# DrivewayLights.net
KiCad netlist of a schematic drawn in EAGLE
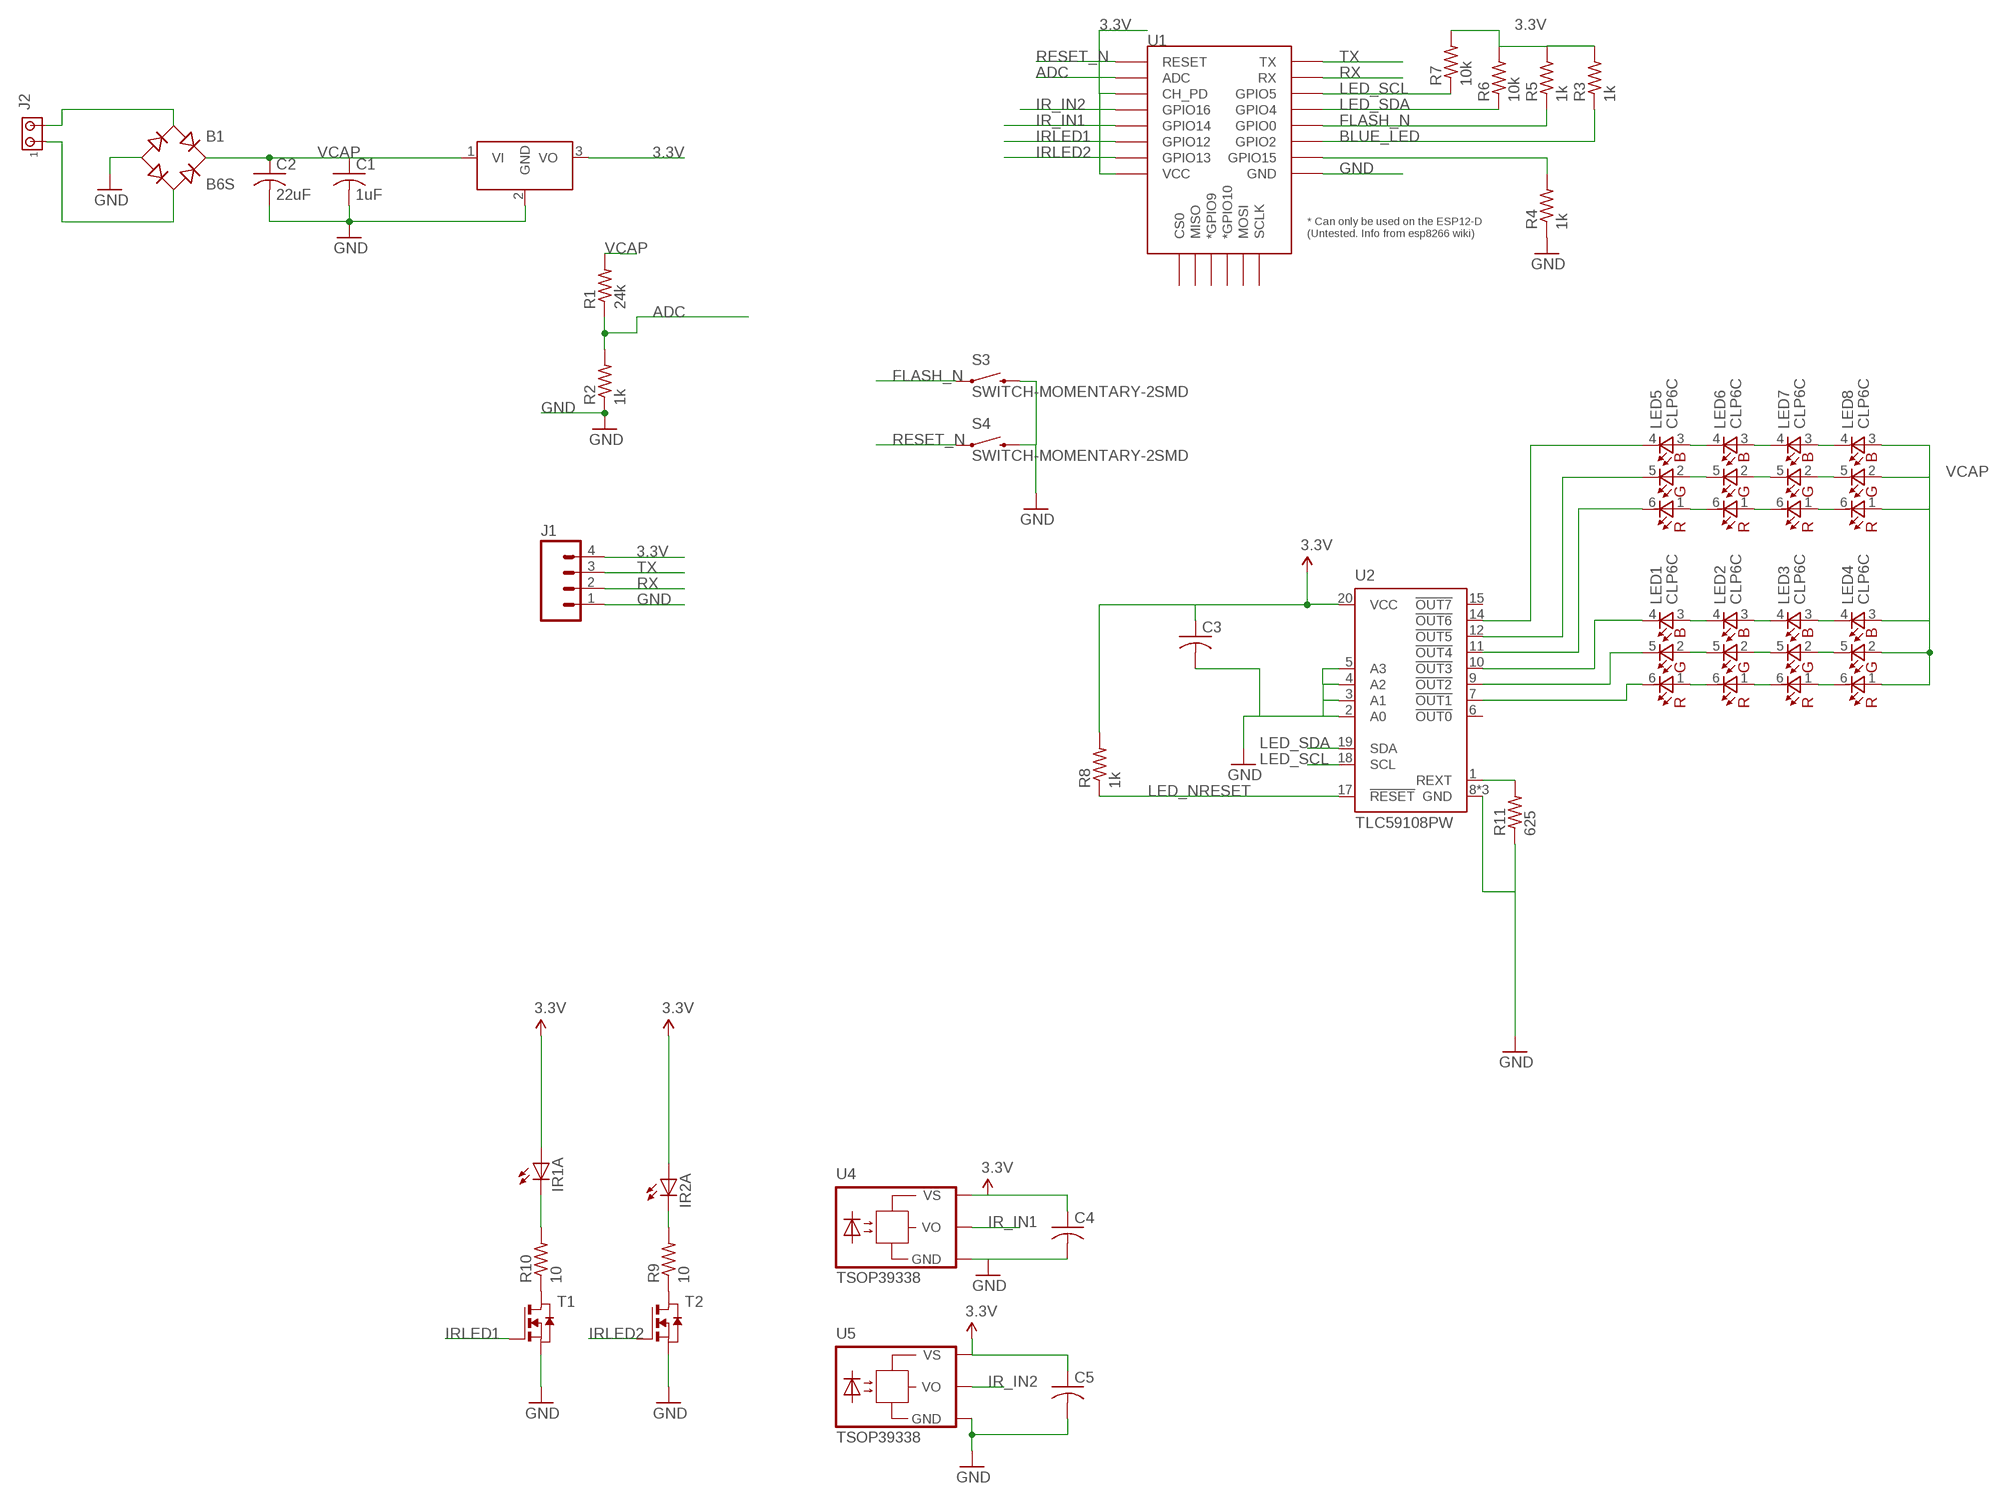
[diagram p0: schematic, sheet 1]

(export (version "E")
  (design (tool "Eeschema 10.0.6"))
  (components
    (comp (ref "B1")
      (value "B6S")
      (footprint "eagle-import:MBS")
      (libsource (lib "eagle-import") (part "BS6"))
    )
    (comp (ref "C1")
      (value "1uF")
      (footprint "eagle-import:C0805")
      (libsource (lib "eagle-import") (part "C-USC0805"))
    )
    (comp (ref "C2")
      (value "22uF")
      (footprint "eagle-import:C1210")
      (libsource (lib "eagle-import") (part "C-USC1210"))
    )
    (comp (ref "C3")
      (value "C-USC0603")
      (footprint "eagle-import:C0603")
      (libsource (lib "eagle-import") (part "C-USC0603"))
    )
    (comp (ref "C4")
      (value "C-USC0603")
      (footprint "eagle-import:C0603")
      (libsource (lib "eagle-import") (part "C-USC0603"))
    )
    (comp (ref "C5")
      (value "C-USC0603")
      (footprint "eagle-import:C0603")
      (libsource (lib "eagle-import") (part "C-USC0603"))
    )
    (comp (ref "IR1A")
      (value "LED5MM")
      (footprint "eagle-import:LED5MM")
      (libsource (lib "eagle-import") (part "LED5MM"))
    )
    (comp (ref "IR2A")
      (value "LED5MM")
      (footprint "eagle-import:LED5MM")
      (libsource (lib "eagle-import") (part "LED5MM"))
    )
    (comp (ref "J1")
      (value "M04JST-PTH-VERT")
      (footprint "eagle-import:JST-4-PTH-VERT")
      (libsource (lib "eagle-import") (part "M04JST-PTH-VERT"))
    )
    (comp (ref "J2")
      (value "MTA02-100")
      (footprint "eagle-import:10X02MTA")
      (libsource (lib "eagle-import") (part "MTA02-100"))
    )
    (comp (ref "LED1")
      (value "CLP6C")
      (footprint "eagle-import:CLP6C")
      (libsource (lib "eagle-import") (part "CLP6C"))
    )
    (comp (ref "LED2")
      (value "CLP6C")
      (footprint "eagle-import:CLP6C")
      (libsource (lib "eagle-import") (part "CLP6C"))
    )
    (comp (ref "LED3")
      (value "CLP6C")
      (footprint "eagle-import:CLP6C")
      (libsource (lib "eagle-import") (part "CLP6C"))
    )
    (comp (ref "LED4")
      (value "CLP6C")
      (footprint "eagle-import:CLP6C")
      (libsource (lib "eagle-import") (part "CLP6C"))
    )
    (comp (ref "LED5")
      (value "CLP6C")
      (footprint "eagle-import:CLP6C")
      (libsource (lib "eagle-import") (part "CLP6C"))
    )
    (comp (ref "LED6")
      (value "CLP6C")
      (footprint "eagle-import:CLP6C")
      (libsource (lib "eagle-import") (part "CLP6C"))
    )
    (comp (ref "LED7")
      (value "CLP6C")
      (footprint "eagle-import:CLP6C")
      (libsource (lib "eagle-import") (part "CLP6C"))
    )
    (comp (ref "LED8")
      (value "CLP6C")
      (footprint "eagle-import:CLP6C")
      (libsource (lib "eagle-import") (part "CLP6C"))
    )
    (comp (ref "R1")
      (value "24k")
      (footprint "eagle-import:R0603")
      (libsource (lib "eagle-import") (part "resistor_R-US_R0603"))
    )
    (comp (ref "R2")
      (value "1k")
      (footprint "eagle-import:R0603")
      (libsource (lib "eagle-import") (part "resistor_R-US_R0603"))
    )
    (comp (ref "R3")
      (value "1k")
      (footprint "eagle-import:R0603")
      (libsource (lib "eagle-import") (part "resistor_R-US_R0603"))
    )
    (comp (ref "R4")
      (value "1k")
      (footprint "eagle-import:R0603")
      (libsource (lib "eagle-import") (part "resistor_R-US_R0603"))
    )
    (comp (ref "R5")
      (value "1k")
      (footprint "eagle-import:R0603")
      (libsource (lib "eagle-import") (part "resistor_R-US_R0603"))
    )
    (comp (ref "R6")
      (value "10k")
      (footprint "eagle-import:R0603")
      (libsource (lib "eagle-import") (part "resistor_R-US_R0603"))
    )
    (comp (ref "R7")
      (value "10k")
      (footprint "eagle-import:R0603")
      (libsource (lib "eagle-import") (part "resistor_R-US_R0603"))
    )
    (comp (ref "R8")
      (value "1k")
      (footprint "eagle-import:R0603")
      (libsource (lib "eagle-import") (part "resistor_R-US_R0603"))
    )
    (comp (ref "R9")
      (value "10")
      (footprint "eagle-import:R0603")
      (libsource (lib "eagle-import") (part "R-US_R0603"))
    )
    (comp (ref "R10")
      (value "10")
      (footprint "eagle-import:R0603")
      (libsource (lib "eagle-import") (part "R-US_R0603"))
    )
    (comp (ref "R11")
      (value "625")
      (footprint "eagle-import:R0603")
      (libsource (lib "eagle-import") (part "R-US_R0603"))
    )
    (comp (ref "S3")
      (value "SWITCH-MOMENTARY-2SMD")
      (footprint "eagle-import:TACTILE-SWITCH-SMD")
      (libsource (lib "eagle-import") (part "SWITCH-MOMENTARY-2SMD"))
    )
    (comp (ref "S4")
      (value "SWITCH-MOMENTARY-2SMD")
      (footprint "eagle-import:TACTILE-SWITCH-SMD")
      (libsource (lib "eagle-import") (part "SWITCH-MOMENTARY-2SMD"))
    )
    (comp (ref "T1")
      (value "NMOSSOT23")
      (footprint "eagle-import:SOT-23")
      (libsource (lib "eagle-import") (part "NMOSSOT23"))
    )
    (comp (ref "T2")
      (value "NMOSSOT23")
      (footprint "eagle-import:SOT-23")
      (libsource (lib "eagle-import") (part "NMOSSOT23"))
    )
    (comp (ref "U1")
      (value "ESP12ESMD")
      (footprint "eagle-import:ESP12E-SMD")
      (libsource (lib "eagle-import") (part "ESP12ESMD"))
    )
    (comp (ref "U2")
      (value "TLC59108PW")
      (footprint "eagle-import:PW_R-PDSO-G20")
      (libsource (lib "eagle-import") (part "TLC59108PW"))
    )
    (comp (ref "U3")
      (value "DCDC_OKI-78SR")
      (footprint "eagle-import:OKI-78SRH")
      (libsource (lib "eagle-import") (part "DCDC_OKI-78SR"))
    )
    (comp (ref "U4")
      (value "TSOP39338")
      (footprint "eagle-import:TSOP39338")
      (libsource (lib "eagle-import") (part "TSOP39338"))
    )
    (comp (ref "U5")
      (value "TSOP39338")
      (footprint "eagle-import:TSOP39338")
      (libsource (lib "eagle-import") (part "TSOP39338"))
    )
  )
  (nets
    (net (code "1") (name "/ADC") (class "Default")
      (node (ref "R1") (pin "1") (pinfunction "1_1") (pintype "passive"))
      (node (ref "R2") (pin "2") (pinfunction "2_2") (pintype "passive"))
      (node (ref "U1") (pin "ADC") (pinfunction "ADC_ADC") (pintype "bidirectional"))
    )
    (net (code "2") (name "/BLUE_LED") (class "Default")
      (node (ref "R3") (pin "1") (pinfunction "1_1") (pintype "passive"))
      (node (ref "U1") (pin "GPIO2") (pinfunction "GPIO2_GPIO2") (pintype "bidirectional"))
    )
    (net (code "3") (name "/FLASH_N") (class "Default")
      (node (ref "R5") (pin "1") (pinfunction "1_1") (pintype "passive"))
      (node (ref "S3") (pin "1") (pinfunction "1_1") (pintype "passive"))
      (node (ref "U1") (pin "GPIO0") (pinfunction "GPIO0_GPIO0") (pintype "bidirectional"))
    )
    (net (code "4") (name "/IRLED1") (class "Default")
      (node (ref "T1") (pin "3") (pinfunction "G_3") (pintype "passive"))
      (node (ref "U1") (pin "GPIO12") (pinfunction "GPIO12_GPIO12") (pintype "bidirectional"))
    )
    (net (code "5") (name "/IRLED2") (class "Default")
      (node (ref "T2") (pin "3") (pinfunction "G_3") (pintype "passive"))
      (node (ref "U1") (pin "GPIO13") (pinfunction "GPIO13_GPIO13") (pintype "bidirectional"))
    )
    (net (code "6") (name "/IR_IN1") (class "Default")
      (node (ref "U1") (pin "GPIO14") (pinfunction "GPIO14_GPIO14") (pintype "bidirectional"))
      (node (ref "U4") (pin "OUT") (pinfunction "VO_OUT") (pintype "open_collector"))
    )
    (net (code "7") (name "/IR_IN2") (class "Default")
      (node (ref "U1") (pin "GPIO16") (pinfunction "GPIO16_GPIO16") (pintype "bidirectional"))
      (node (ref "U5") (pin "OUT") (pinfunction "VO_OUT") (pintype "open_collector"))
    )
    (net (code "8") (name "/LED_NRESET") (class "Default")
      (node (ref "R8") (pin "1") (pinfunction "1_1") (pintype "passive"))
      (node (ref "U2") (pin "17") (pinfunction "~{RESET}_17") (pintype "input"))
    )
    (net (code "9") (name "/LED_SCL") (class "Default")
      (node (ref "R7") (pin "1") (pinfunction "1_1") (pintype "passive"))
      (node (ref "U1") (pin "GPIO5") (pinfunction "GPIO5_GPIO5") (pintype "bidirectional"))
      (node (ref "U2") (pin "18") (pinfunction "SCL_18") (pintype "bidirectional"))
    )
    (net (code "10") (name "/LED_SDA") (class "Default")
      (node (ref "R6") (pin "1") (pinfunction "1_1") (pintype "passive"))
      (node (ref "U1") (pin "GPIO4") (pinfunction "GPIO4_GPIO4") (pintype "bidirectional"))
      (node (ref "U2") (pin "19") (pinfunction "SDA_19") (pintype "bidirectional"))
    )
    (net (code "11") (name "/RESET_N") (class "Default")
      (node (ref "S4") (pin "1") (pinfunction "1_1") (pintype "passive"))
      (node (ref "U1") (pin "RESET") (pinfunction "RESET_RESET") (pintype "bidirectional"))
    )
    (net (code "12") (name "/RX") (class "Default")
      (node (ref "J1") (pin "2") (pinfunction "2_2") (pintype "passive"))
      (node (ref "U1") (pin "RXD0") (pinfunction "RX_RXD0") (pintype "bidirectional"))
    )
    (net (code "13") (name "/TX") (class "Default")
      (node (ref "J1") (pin "3") (pinfunction "3_3") (pintype "passive"))
      (node (ref "U1") (pin "TXD0") (pinfunction "TX_TXD0") (pintype "bidirectional"))
    )
    (net (code "14") (name "/VCAP") (class "Default")
      (node (ref "B1") (pin "+") (pinfunction "+_+") (pintype "passive"))
      (node (ref "C1") (pin "1") (pinfunction "1_1") (pintype "passive"))
      (node (ref "C2") (pin "1") (pinfunction "1_1") (pintype "passive"))
      (node (ref "LED4") (pin "1") (pinfunction "RA_1") (pintype "passive"))
      (node (ref "LED4") (pin "2") (pinfunction "GA_2") (pintype "passive"))
      (node (ref "LED4") (pin "3") (pinfunction "BA_3") (pintype "passive"))
      (node (ref "LED8") (pin "1") (pinfunction "RA_1") (pintype "passive"))
      (node (ref "LED8") (pin "2") (pinfunction "GA_2") (pintype "passive"))
      (node (ref "LED8") (pin "3") (pinfunction "BA_3") (pintype "passive"))
      (node (ref "R1") (pin "2") (pinfunction "2_2") (pintype "passive"))
      (node (ref "U3") (pin "1") (pinfunction "VI_1") (pintype "bidirectional"))
    )
    (net (code "15") (name "3.3V") (class "Default")
      (node (ref "C3") (pin "1") (pinfunction "1_1") (pintype "passive"))
      (node (ref "C4") (pin "1") (pinfunction "1_1") (pintype "passive"))
      (node (ref "C5") (pin "1") (pinfunction "1_1") (pintype "passive"))
      (node (ref "IR1A") (pin "A") (pinfunction "A_A") (pintype "passive"))
      (node (ref "IR2A") (pin "A") (pinfunction "A_A") (pintype "passive"))
      (node (ref "J1") (pin "4") (pinfunction "4_4") (pintype "passive"))
      (node (ref "R3") (pin "2") (pinfunction "2_2") (pintype "passive"))
      (node (ref "R5") (pin "2") (pinfunction "2_2") (pintype "passive"))
      (node (ref "R6") (pin "2") (pinfunction "2_2") (pintype "passive"))
      (node (ref "R7") (pin "2") (pinfunction "2_2") (pintype "passive"))
      (node (ref "R8") (pin "2") (pinfunction "2_2") (pintype "passive"))
      (node (ref "U1") (pin "CH_PD") (pinfunction "CH_PD_CH_PD") (pintype "bidirectional"))
      (node (ref "U1") (pin "VCC") (pinfunction "VCC_VCC") (pintype "bidirectional"))
      (node (ref "U2") (pin "20") (pinfunction "VCC_20") (pintype "power_in"))
      (node (ref "U3") (pin "3") (pinfunction "VO_3") (pintype "bidirectional"))
      (node (ref "U4") (pin "VS") (pinfunction "VS_VS") (pintype "power_in"))
      (node (ref "U5") (pin "VS") (pinfunction "VS_VS") (pintype "power_in"))
    )
    (net (code "16") (name "GND") (class "Default")
      (node (ref "B1") (pin "-") (pinfunction "-_-") (pintype "passive"))
      (node (ref "C1") (pin "2") (pinfunction "2_2") (pintype "passive"))
      (node (ref "C2") (pin "2") (pinfunction "2_2") (pintype "passive"))
      (node (ref "C3") (pin "2") (pinfunction "2_2") (pintype "passive"))
      (node (ref "C4") (pin "2") (pinfunction "2_2") (pintype "passive"))
      (node (ref "C5") (pin "2") (pinfunction "2_2") (pintype "passive"))
      (node (ref "J1") (pin "1") (pinfunction "1_1") (pintype "passive"))
      (node (ref "R11") (pin "1") (pinfunction "1_1") (pintype "passive"))
      (node (ref "R2") (pin "1") (pinfunction "1_1") (pintype "passive"))
      (node (ref "R4") (pin "1") (pinfunction "1_1") (pintype "passive"))
      (node (ref "S3") (pin "3") (pinfunction "2_3") (pintype "passive"))
      (node (ref "S4") (pin "3") (pinfunction "2_3") (pintype "passive"))
      (node (ref "T1") (pin "2") (pinfunction "S_2") (pintype "passive"))
      (node (ref "T2") (pin "2") (pinfunction "S_2") (pintype "passive"))
      (node (ref "U1") (pin "GND") (pinfunction "GND_GND") (pintype "bidirectional"))
      (node (ref "U2") (pin "13") (pinfunction "GND_13") (pintype "power_in"))
      (node (ref "U2") (pin "16") (pinfunction "GND_16") (pintype "power_in"))
      (node (ref "U2") (pin "2") (pinfunction "A0_2") (pintype "input"))
      (node (ref "U2") (pin "3") (pinfunction "A1_3") (pintype "input"))
      (node (ref "U2") (pin "4") (pinfunction "A2_4") (pintype "input"))
      (node (ref "U2") (pin "5") (pinfunction "A3_5") (pintype "input"))
      (node (ref "U2") (pin "8") (pinfunction "GND_8") (pintype "power_in"))
      (node (ref "U3") (pin "2") (pinfunction "GND_2") (pintype "bidirectional"))
      (node (ref "U4") (pin "GND") (pinfunction "GND_GND") (pintype "power_in"))
      (node (ref "U5") (pin "GND") (pinfunction "GND_GND") (pintype "power_in"))
    )
    (net (code "17") (name "Net-(B1-PadAC1)") (class "Default")
      (node (ref "B1") (pin "AC1") (pinfunction "AC1_AC1") (pintype "passive"))
      (node (ref "J2") (pin "2") (pinfunction "2_2") (pintype "passive"))
    )
    (net (code "18") (name "Net-(B1-PadAC2)") (class "Default")
      (node (ref "B1") (pin "AC2") (pinfunction "AC2_AC2") (pintype "passive"))
      (node (ref "J2") (pin "1") (pinfunction "1_1") (pintype "passive"))
    )
    (net (code "19") (name "Net-(IR1A-C)") (class "Default")
      (node (ref "IR1A") (pin "K") (pinfunction "C_K") (pintype "passive"))
      (node (ref "R10") (pin "2") (pinfunction "2_2") (pintype "passive"))
    )
    (net (code "20") (name "Net-(IR2A-C)") (class "Default")
      (node (ref "IR2A") (pin "K") (pinfunction "C_K") (pintype "passive"))
      (node (ref "R9") (pin "2") (pinfunction "2_2") (pintype "passive"))
    )
    (net (code "21") (name "Net-(LED1-BA)") (class "Default")
      (node (ref "LED1") (pin "3") (pinfunction "BA_3") (pintype "passive"))
      (node (ref "LED2") (pin "4") (pinfunction "BC_4") (pintype "passive"))
    )
    (net (code "22") (name "Net-(LED1-BC)") (class "Default")
      (node (ref "LED1") (pin "4") (pinfunction "BC_4") (pintype "passive"))
      (node (ref "U2") (pin "10") (pinfunction "~{OUT3}_10") (pintype "output"))
    )
    (net (code "23") (name "Net-(LED1-GA)") (class "Default")
      (node (ref "LED1") (pin "2") (pinfunction "GA_2") (pintype "passive"))
      (node (ref "LED2") (pin "5") (pinfunction "GC_5") (pintype "passive"))
    )
    (net (code "24") (name "Net-(LED1-GC)") (class "Default")
      (node (ref "LED1") (pin "5") (pinfunction "GC_5") (pintype "passive"))
      (node (ref "U2") (pin "9") (pinfunction "~{OUT2}_9") (pintype "output"))
    )
    (net (code "25") (name "Net-(LED1-RA)") (class "Default")
      (node (ref "LED1") (pin "1") (pinfunction "RA_1") (pintype "passive"))
      (node (ref "LED2") (pin "6") (pinfunction "RC_6") (pintype "passive"))
    )
    (net (code "26") (name "Net-(LED1-RC)") (class "Default")
      (node (ref "LED1") (pin "6") (pinfunction "RC_6") (pintype "passive"))
      (node (ref "U2") (pin "7") (pinfunction "~{OUT1}_7") (pintype "output"))
    )
    (net (code "27") (name "Net-(LED2-BA)") (class "Default")
      (node (ref "LED2") (pin "3") (pinfunction "BA_3") (pintype "passive"))
      (node (ref "LED3") (pin "4") (pinfunction "BC_4") (pintype "passive"))
    )
    (net (code "28") (name "Net-(LED2-GA)") (class "Default")
      (node (ref "LED2") (pin "2") (pinfunction "GA_2") (pintype "passive"))
      (node (ref "LED3") (pin "5") (pinfunction "GC_5") (pintype "passive"))
    )
    (net (code "29") (name "Net-(LED2-RA)") (class "Default")
      (node (ref "LED2") (pin "1") (pinfunction "RA_1") (pintype "passive"))
      (node (ref "LED3") (pin "6") (pinfunction "RC_6") (pintype "passive"))
    )
    (net (code "30") (name "Net-(LED3-BA)") (class "Default")
      (node (ref "LED3") (pin "3") (pinfunction "BA_3") (pintype "passive"))
      (node (ref "LED4") (pin "4") (pinfunction "BC_4") (pintype "passive"))
    )
    (net (code "31") (name "Net-(LED3-GA)") (class "Default")
      (node (ref "LED3") (pin "2") (pinfunction "GA_2") (pintype "passive"))
      (node (ref "LED4") (pin "5") (pinfunction "GC_5") (pintype "passive"))
    )
    (net (code "32") (name "Net-(LED3-RA)") (class "Default")
      (node (ref "LED3") (pin "1") (pinfunction "RA_1") (pintype "passive"))
      (node (ref "LED4") (pin "6") (pinfunction "RC_6") (pintype "passive"))
    )
    (net (code "33") (name "Net-(LED5-BA)") (class "Default")
      (node (ref "LED5") (pin "3") (pinfunction "BA_3") (pintype "passive"))
      (node (ref "LED6") (pin "4") (pinfunction "BC_4") (pintype "passive"))
    )
    (net (code "34") (name "Net-(LED5-BC)") (class "Default")
      (node (ref "LED5") (pin "4") (pinfunction "BC_4") (pintype "passive"))
      (node (ref "U2") (pin "14") (pinfunction "~{OUT6}_14") (pintype "output"))
    )
    (net (code "35") (name "Net-(LED5-GA)") (class "Default")
      (node (ref "LED5") (pin "2") (pinfunction "GA_2") (pintype "passive"))
      (node (ref "LED6") (pin "5") (pinfunction "GC_5") (pintype "passive"))
    )
    (net (code "36") (name "Net-(LED5-GC)") (class "Default")
      (node (ref "LED5") (pin "5") (pinfunction "GC_5") (pintype "passive"))
      (node (ref "U2") (pin "12") (pinfunction "~{OUT5}_12") (pintype "output"))
    )
    (net (code "37") (name "Net-(LED5-RA)") (class "Default")
      (node (ref "LED5") (pin "1") (pinfunction "RA_1") (pintype "passive"))
      (node (ref "LED6") (pin "6") (pinfunction "RC_6") (pintype "passive"))
    )
    (net (code "38") (name "Net-(LED5-RC)") (class "Default")
      (node (ref "LED5") (pin "6") (pinfunction "RC_6") (pintype "passive"))
      (node (ref "U2") (pin "11") (pinfunction "~{OUT4}_11") (pintype "output"))
    )
    (net (code "39") (name "Net-(LED6-BA)") (class "Default")
      (node (ref "LED6") (pin "3") (pinfunction "BA_3") (pintype "passive"))
      (node (ref "LED7") (pin "4") (pinfunction "BC_4") (pintype "passive"))
    )
    (net (code "40") (name "Net-(LED6-GA)") (class "Default")
      (node (ref "LED6") (pin "2") (pinfunction "GA_2") (pintype "passive"))
      (node (ref "LED7") (pin "5") (pinfunction "GC_5") (pintype "passive"))
    )
    (net (code "41") (name "Net-(LED6-RA)") (class "Default")
      (node (ref "LED6") (pin "1") (pinfunction "RA_1") (pintype "passive"))
      (node (ref "LED7") (pin "6") (pinfunction "RC_6") (pintype "passive"))
    )
    (net (code "42") (name "Net-(LED7-BA)") (class "Default")
      (node (ref "LED7") (pin "3") (pinfunction "BA_3") (pintype "passive"))
      (node (ref "LED8") (pin "4") (pinfunction "BC_4") (pintype "passive"))
    )
    (net (code "43") (name "Net-(LED7-GA)") (class "Default")
      (node (ref "LED7") (pin "2") (pinfunction "GA_2") (pintype "passive"))
      (node (ref "LED8") (pin "5") (pinfunction "GC_5") (pintype "passive"))
    )
    (net (code "44") (name "Net-(LED7-RA)") (class "Default")
      (node (ref "LED7") (pin "1") (pinfunction "RA_1") (pintype "passive"))
      (node (ref "LED8") (pin "6") (pinfunction "RC_6") (pintype "passive"))
    )
    (net (code "45") (name "Net-(R4-Pad2)") (class "Default")
      (node (ref "R4") (pin "2") (pinfunction "2_2") (pintype "passive"))
      (node (ref "U1") (pin "GPIO15") (pinfunction "GPIO15_GPIO15") (pintype "bidirectional"))
    )
    (net (code "46") (name "Net-(T1-D)") (class "Default")
      (node (ref "R10") (pin "1") (pinfunction "1_1") (pintype "passive"))
      (node (ref "T1") (pin "1") (pinfunction "D_1") (pintype "passive"))
    )
    (net (code "47") (name "Net-(T2-D)") (class "Default")
      (node (ref "R9") (pin "1") (pinfunction "1_1") (pintype "passive"))
      (node (ref "T2") (pin "1") (pinfunction "D_1") (pintype "passive"))
    )
    (net (code "48") (name "Net-(U2-REXT)") (class "Default")
      (node (ref "R11") (pin "2") (pinfunction "2_2") (pintype "passive"))
      (node (ref "U2") (pin "1") (pinfunction "REXT_1") (pintype "passive"))
    )
    (net (code "49") (name "unconnected-(U1-*GPIO9-PadGPIO9)") (class "Default")
      (node (ref "U1") (pin "GPIO9") (pinfunction "*GPIO9_GPIO9") (pintype "bidirectional"))
    )
    (net (code "50") (name "unconnected-(U1-*GPIO10-PadGPIO10)") (class "Default")
      (node (ref "U1") (pin "GPIO10") (pinfunction "*GPIO10_GPIO10") (pintype "bidirectional"))
    )
    (net (code "51") (name "unconnected-(U1-PadCS0)") (class "Default")
      (node (ref "U1") (pin "CS0") (pinfunction "CS0_CS0") (pintype "bidirectional"))
    )
    (net (code "52") (name "unconnected-(U1-PadMISO)") (class "Default")
      (node (ref "U1") (pin "MISO") (pinfunction "MISO_MISO") (pintype "bidirectional"))
    )
    (net (code "53") (name "unconnected-(U1-PadMOSI)") (class "Default")
      (node (ref "U1") (pin "MOSI") (pinfunction "MOSI_MOSI") (pintype "bidirectional"))
    )
    (net (code "54") (name "unconnected-(U1-PadSCLK)") (class "Default")
      (node (ref "U1") (pin "SCLK") (pinfunction "SCLK_SCLK") (pintype "bidirectional"))
    )
    (net (code "55") (name "unconnected-(U2-~{OUT0}-Pad6)") (class "Default")
      (node (ref "U2") (pin "6") (pinfunction "~{OUT0}_6") (pintype "output"))
    )
    (net (code "56") (name "unconnected-(U2-~{OUT7}-Pad15)") (class "Default")
      (node (ref "U2") (pin "15") (pinfunction "~{OUT7}_15") (pintype "output"))
    )
  )
)
